# dds.net
KiCad netlist of a schematic drawn in Altium Designer
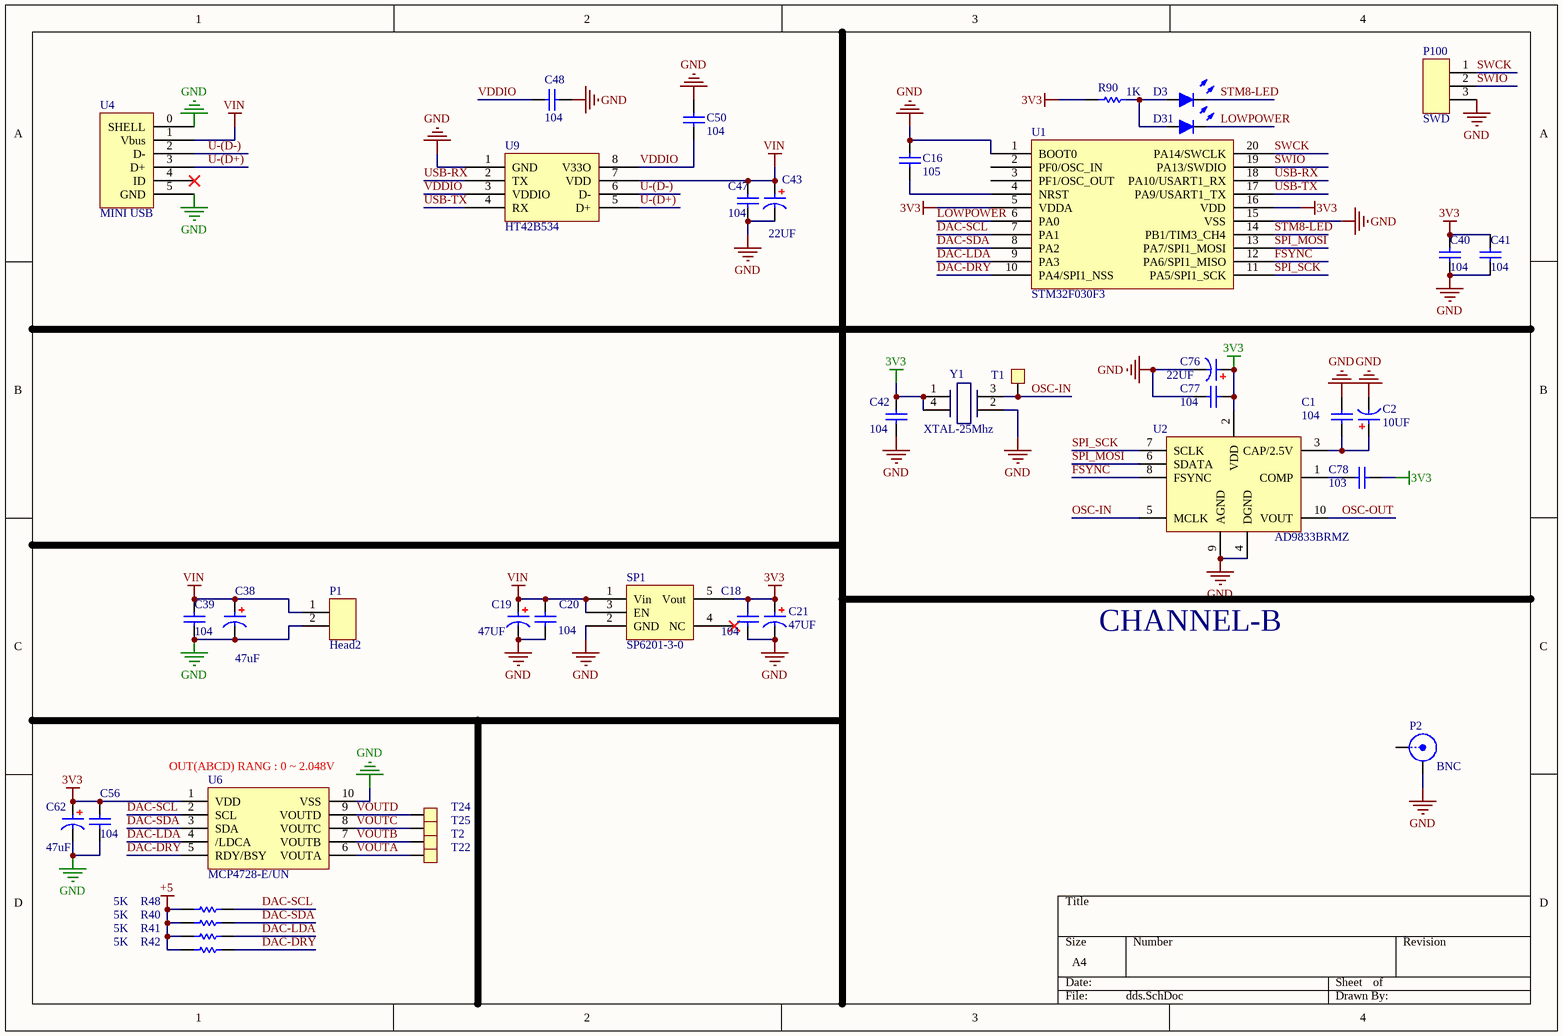
[diagram p0: dds.SchDoc]

(export (version "E")
  (design (tool "Eeschema 10.0.6"))
  (components
    (comp (ref "C1")
      (value "C104")
      (footprint "0402")
      (description "贴片电容")
      (fields (field (name "ALTIUM_UNNAMED_1") "104"))
      (libsource (lib "OKmeSchLibrary") (part "C0.1uF"))
    )
    (comp (ref "C2")
      (value "10UF")
      (footprint "0603C")
      (description "贴片电容")
      (fields (field (name "ALTIUM_UNNAMED_1") "10UF"))
      (libsource (lib "") (part "C10uF_1"))
    )
    (comp (ref "C16")
      (value "C1uF")
      (footprint "0603C")
      (fields (field (name "ALTIUM_UNNAMED_1") "105"))
      (libsource (lib "OKmeSchLibrary") (part "C0.1uF"))
    )
    (comp (ref "C18")
      (value "C104")
      (footprint "0402")
      (description "贴片电容")
      (fields (field (name "ALTIUM_UNNAMED_1") "104"))
      (libsource (lib "OKmeSchLibrary") (part "C0.1uF"))
    )
    (comp (ref "C19")
      (value "47UF")
      (footprint "CAP-T-3216")
      (description "贴片电容")
      (fields (field (name "ALTIUM_UNNAMED_1") "47UF"))
      (libsource (lib "") (part "C10uF_1"))
    )
    (comp (ref "C20")
      (value "C104")
      (footprint "0402")
      (description "贴片电容")
      (fields (field (name "ALTIUM_UNNAMED_1") "104"))
      (libsource (lib "OKmeSchLibrary") (part "C0.1uF"))
    )
    (comp (ref "C21")
      (value "47UF")
      (footprint "CAP-T-3216")
      (description "贴片电容")
      (fields (field (name "ALTIUM_UNNAMED_1") "47UF"))
      (libsource (lib "") (part "C10uF_1"))
    )
    (comp (ref "C38")
      (value "47uF")
      (footprint "CAP-T-3216")
      (description "贴片电容")
      (fields (field (name "ALTIUM_UNNAMED_1") "47uF"))
      (libsource (lib "") (part "C10uF_1"))
    )
    (comp (ref "C39")
      (value "C0.1uF")
      (footprint "0402")
      (fields (field (name "ALTIUM_UNNAMED_1") "104"))
      (libsource (lib "OKmeSchLibrary") (part "C0.1uF"))
    )
    (comp (ref "C40")
      (value "C0.1uF")
      (footprint "0402")
      (fields (field (name "ALTIUM_UNNAMED_1") "104"))
      (libsource (lib "OKmeSchLibrary") (part "C0.1uF"))
    )
    (comp (ref "C41")
      (value "C0.1uF")
      (footprint "0402")
      (fields (field (name "ALTIUM_UNNAMED_1") "104"))
      (libsource (lib "OKmeSchLibrary") (part "C0.1uF"))
    )
    (comp (ref "C42")
      (value "C0.1uF")
      (footprint "0402")
      (fields (field (name "ALTIUM_UNNAMED_1") "104"))
      (libsource (lib "OKmeSchLibrary") (part "C0.1uF"))
    )
    (comp (ref "C43")
      (value "22UF")
      (footprint "0603C")
      (fields (field (name "ALTIUM_UNNAMED_1") "22UF"))
      (libsource (lib "OKmeSchLibrary") (part "C100uF"))
    )
    (comp (ref "C47")
      (value "104")
      (footprint "0402")
      (fields (field (name "ALTIUM_UNNAMED_1") "104"))
      (libsource (lib "OKmeSchLibrary") (part "C0.1uF"))
    )
    (comp (ref "C48")
      (value "104")
      (footprint "0402")
      (fields (field (name "ALTIUM_UNNAMED_1") "104"))
      (libsource (lib "OKmeSchLibrary") (part "C0.1uF"))
    )
    (comp (ref "C50")
      (value "104")
      (footprint "0402")
      (fields (field (name "ALTIUM_UNNAMED_1") "104"))
      (libsource (lib "OKmeSchLibrary") (part "C0.1uF"))
    )
    (comp (ref "C56")
      (value "C0.1uF")
      (footprint "0402")
      (fields (field (name "ALTIUM_UNNAMED_1") "104"))
      (libsource (lib "OKmeSchLibrary") (part "C0.1uF"))
    )
    (comp (ref "C62")
      (value "47uF")
      (footprint "CAP-T-3216")
      (description "贴片电容")
      (fields (field (name "ALTIUM_UNNAMED_1") "47uF"))
      (libsource (lib "") (part "C10uF_1"))
    )
    (comp (ref "C76")
      (value "22UF")
      (footprint "0603C")
      (description "贴片电容")
      (fields (field (name "ALTIUM_UNNAMED_1") "22UF"))
      (libsource (lib "OKmeSchLibrary") (part "C10uF"))
    )
    (comp (ref "C77")
      (value "C104")
      (footprint "0402")
      (description "贴片电容")
      (fields (field (name "ALTIUM_UNNAMED_1") "104"))
      (libsource (lib "OKmeSchLibrary") (part "C0.1uF"))
    )
    (comp (ref "C78")
      (value "C103")
      (footprint "0402")
      (description "贴片电容")
      (fields (field (name "ALTIUM_UNNAMED_1") "103"))
      (libsource (lib "OKmeSchLibrary") (part "C0.1uF"))
    )
    (comp (ref "D3") (value "LED-G") (footprint "LED") (libsource (lib "OKmeSchLibrary") (part "LED")))
    (comp (ref "D31") (value "LED-R") (footprint "LED") (libsource (lib "OKmeSchLibrary") (part "LED")))
    (comp (ref "P1") (value "Head2") (footprint "HEAD2") (libsource (lib "OKmeSchLibrary") (part "Head2")))
    (comp (ref "P2")
      (value "BNC")
      (footprint "BNC-OSC")
      (description "BNC Elbow Connector")
      (fields (field (name "PUBLISHER") "Altium Limited"))
      (libsource (lib "Miscellaneous Connectors") (part "BNC"))
    )
    (comp (ref "P100")
      (value "SWD")
      (footprint "head*3 - duplicate")
      (libsource (lib "OKmeSchLibrary") (part "head*3"))
    )
    (comp (ref "R40")
      (value "R5K")
      (footprint "0402")
      (fields (field (name "ALTIUM_UNNAMED_1") "5K"))
      (libsource (lib "OKmeSchLibrary") (part "R10K"))
    )
    (comp (ref "R41")
      (value "R5K")
      (footprint "0402")
      (fields (field (name "ALTIUM_UNNAMED_1") "5K"))
      (libsource (lib "OKmeSchLibrary") (part "R10K"))
    )
    (comp (ref "R42")
      (value "R5K")
      (footprint "0402")
      (fields (field (name "ALTIUM_UNNAMED_1") "5K"))
      (libsource (lib "OKmeSchLibrary") (part "R10K"))
    )
    (comp (ref "R48")
      (value "R5K")
      (footprint "0402")
      (fields (field (name "ALTIUM_UNNAMED_1") "5K"))
      (libsource (lib "OKmeSchLibrary") (part "R10K"))
    )
    (comp (ref "R90")
      (value "R1K")
      (footprint "0603R")
      (fields (field (name "ALTIUM_UNNAMED_1") "1K"))
      (libsource (lib "OKmeSchLibrary") (part "R1K"))
    )
    (comp (ref "SP1")
      (value "SP6201-3-0")
      (footprint "SOT23-5")
      (libsource (lib "OKmeSchLibrary") (part "SP6201"))
    )
    (comp (ref "T1") (value "TP") (footprint "TEST_POINT") (libsource (lib "") (part "TP_1")))
    (comp (ref "T2") (value "TP") (footprint "TEST_POINT") (libsource (lib "OKmeSchLibrary") (part "TP")))
    (comp (ref "T22") (value "TP") (footprint "TEST_POINT") (libsource (lib "OKmeSchLibrary") (part "TP")))
    (comp (ref "T24") (value "TP") (footprint "TEST_POINT") (libsource (lib "OKmeSchLibrary") (part "TP")))
    (comp (ref "T25") (value "TP") (footprint "TEST_POINT") (libsource (lib "OKmeSchLibrary") (part "TP")))
    (comp (ref "U1")
      (value "STM32F030F3")
      (footprint "TSSOP20")
      (libsource (lib "OKmeSchLibrary") (part "STM32F030F4"))
    )
    (comp (ref "U2") (value "AD9833BRMZ") (footprint "MSOP10") (libsource (lib "osc_dev") (part "AD9833")))
    (comp (ref "U4")
      (value "MINI USB")
      (footprint "Micro_USB_t")
      (libsource (lib "OKmeSchLibrary") (part "MINI USB"))
    )
    (comp (ref "U6")
      (value "MCP4728-E/UN")
      (footprint "MSOP10")
      (libsource (lib "osc_dev") (part "MCP4728-E/UN"))
    )
    (comp (ref "U9")
      (value "HT42B534")
      (footprint "SOP-8")
      (libsource (lib "OKmeSchLibrary") (part "HT42B534"))
    )
    (comp (ref "Y1")
      (value "XTAL-25Mhz")
      (footprint "XTAL3225")
      (libsource (lib "osc_dev") (part "XTAL-100Mhz"))
    )
  )
  (nets
    (net (code "1") (name "+5") (class "Default")
      (node (ref "R40") (pin "1") (pinfunction "1_1") (pintype "passive"))
      (node (ref "R41") (pin "1") (pinfunction "1_1") (pintype "passive"))
      (node (ref "R42") (pin "1") (pinfunction "1_1") (pintype "passive"))
      (node (ref "R48") (pin "2") (pinfunction "2_2") (pintype "passive"))
    )
    (net (code "2") (name "/DAC-DRY") (class "Default")
      (node (ref "R42") (pin "2") (pinfunction "2_2") (pintype "passive"))
      (node (ref "U1") (pin "10") (pinfunction "PA4/SPI1_NSS_10") (pintype "passive"))
      (node (ref "U6") (pin "5") (pinfunction "RDY/BSY_5") (pintype "passive"))
    )
    (net (code "3") (name "/DAC-LDA") (class "Default")
      (node (ref "R41") (pin "2") (pinfunction "2_2") (pintype "passive"))
      (node (ref "U1") (pin "9") (pinfunction "PA3_9") (pintype "passive"))
      (node (ref "U6") (pin "4") (pinfunction "/LDCA_4") (pintype "passive"))
    )
    (net (code "4") (name "/DAC-SCL") (class "Default")
      (node (ref "R48") (pin "1") (pinfunction "1_1") (pintype "passive"))
      (node (ref "U1") (pin "7") (pinfunction "PA1_7") (pintype "passive"))
      (node (ref "U6") (pin "2") (pinfunction "SCL_2") (pintype "passive"))
    )
    (net (code "5") (name "/DAC-SDA") (class "Default")
      (node (ref "R40") (pin "2") (pinfunction "2_2") (pintype "passive"))
      (node (ref "U1") (pin "8") (pinfunction "PA2_8") (pintype "passive"))
      (node (ref "U6") (pin "3") (pinfunction "SDA_3") (pintype "passive"))
    )
    (net (code "6") (name "/FSYNC") (class "Default")
      (node (ref "U1") (pin "12") (pinfunction "PA6/SPI1_MISO_12") (pintype "passive"))
      (node (ref "U2") (pin "8") (pinfunction "FSYNC_8") (pintype "passive"))
    )
    (net (code "7") (name "/LOWPOWER") (class "Default")
      (node (ref "D31") (pin "2") (pinfunction "K_2") (pintype "passive"))
      (node (ref "U1") (pin "6") (pinfunction "PA0_6") (pintype "passive"))
    )
    (net (code "8") (name "/OSC-IN") (class "Default")
      (node (ref "T1") (pin "1") (pinfunction "R_1") (pintype "passive"))
      (node (ref "U2") (pin "5") (pinfunction "MCLK_5") (pintype "passive"))
      (node (ref "Y1") (pin "3") (pinfunction "3_3") (pintype "passive"))
    )
    (net (code "9") (name "/OSC-OUT") (class "Default")
      (node (ref "U2") (pin "10") (pinfunction "VOUT_10") (pintype "passive"))
    )
    (net (code "10") (name "/SPI_MOSI") (class "Default")
      (node (ref "U1") (pin "13") (pinfunction "PA7/SPI1_MOSI_13") (pintype "passive"))
      (node (ref "U2") (pin "6") (pinfunction "SDATA_6") (pintype "passive"))
    )
    (net (code "11") (name "/SPI_SCK") (class "Default")
      (node (ref "U1") (pin "11") (pinfunction "PA5/SPI1_SCK_11") (pintype "passive"))
      (node (ref "U2") (pin "7") (pinfunction "SCLK_7") (pintype "passive"))
    )
    (net (code "12") (name "/STM8-LED") (class "Default")
      (node (ref "D3") (pin "2") (pinfunction "K_2") (pintype "passive"))
      (node (ref "U1") (pin "14") (pinfunction "PB1/TIM3_CH4_14") (pintype "passive"))
    )
    (net (code "13") (name "/SWCK") (class "Default")
      (node (ref "P100") (pin "1") (pinfunction "1_1") (pintype "passive"))
      (node (ref "U1") (pin "20") (pinfunction "PA14/SWCLK_20") (pintype "passive"))
    )
    (net (code "14") (name "/SWIO") (class "Default")
      (node (ref "P100") (pin "2") (pinfunction "2_2") (pintype "passive"))
      (node (ref "U1") (pin "19") (pinfunction "PA13/SWDIO_19") (pintype "passive"))
    )
    (net (code "15") (name "/U-(D+)") (class "Default")
      (node (ref "U4") (pin "3") (pinfunction "D+_3") (pintype "passive"))
      (node (ref "U9") (pin "5") (pinfunction "D+_5") (pintype "passive"))
    )
    (net (code "16") (name "/U-(D-)") (class "Default")
      (node (ref "U4") (pin "2") (pinfunction "D-_2") (pintype "passive"))
      (node (ref "U9") (pin "6") (pinfunction "D-_6") (pintype "passive"))
    )
    (net (code "17") (name "/USB-RX") (class "Default")
      (node (ref "U1") (pin "18") (pinfunction "PA10/USART1_RX_18") (pintype "passive"))
      (node (ref "U9") (pin "2") (pinfunction "TX_2") (pintype "passive"))
    )
    (net (code "18") (name "/USB-TX") (class "Default")
      (node (ref "U1") (pin "17") (pinfunction "PA9/USART1_TX_17") (pintype "passive"))
      (node (ref "U9") (pin "4") (pinfunction "RX_4") (pintype "passive"))
    )
    (net (code "19") (name "/VDDIO") (class "Default")
      (node (ref "C48") (pin "1") (pinfunction "1_1") (pintype "passive"))
      (node (ref "C50") (pin "1") (pinfunction "1_1") (pintype "passive"))
      (node (ref "U9") (pin "3") (pinfunction "VDDIO_3") (pintype "passive"))
      (node (ref "U9") (pin "8") (pinfunction "V33O_8") (pintype "passive"))
    )
    (net (code "20") (name "/VOUTA") (class "Default")
      (node (ref "T22") (pin "1") (pinfunction "R_1") (pintype "passive"))
      (node (ref "U6") (pin "6") (pinfunction "VOUTA_6") (pintype "passive"))
    )
    (net (code "21") (name "/VOUTB") (class "Default")
      (node (ref "T2") (pin "1") (pinfunction "R_1") (pintype "passive"))
      (node (ref "U6") (pin "7") (pinfunction "VOUTB_7") (pintype "passive"))
    )
    (net (code "22") (name "/VOUTC") (class "Default")
      (node (ref "T25") (pin "1") (pinfunction "R_1") (pintype "passive"))
      (node (ref "U6") (pin "8") (pinfunction "VOUTC_8") (pintype "passive"))
    )
    (net (code "23") (name "/VOUTD") (class "Default")
      (node (ref "T24") (pin "1") (pinfunction "R_1") (pintype "passive"))
      (node (ref "U6") (pin "9") (pinfunction "VOUTD_9") (pintype "passive"))
    )
    (net (code "24") (name "3V3") (class "Default")
      (node (ref "C18") (pin "1") (pinfunction "1_1") (pintype "passive"))
      (node (ref "C21") (pin "1") (pinfunction "1_1") (pintype "passive"))
      (node (ref "C40") (pin "1") (pinfunction "1_1") (pintype "passive"))
      (node (ref "C41") (pin "1") (pinfunction "1_1") (pintype "passive"))
      (node (ref "C42") (pin "2") (pinfunction "2_2") (pintype "passive"))
      (node (ref "C56") (pin "1") (pinfunction "1_1") (pintype "passive"))
      (node (ref "C62") (pin "1") (pinfunction "1_1") (pintype "passive"))
      (node (ref "C76") (pin "1") (pinfunction "1_1") (pintype "passive"))
      (node (ref "C77") (pin "1") (pinfunction "1_1") (pintype "passive"))
      (node (ref "C78") (pin "1") (pinfunction "1_1") (pintype "passive"))
      (node (ref "R90") (pin "1") (pinfunction "1_1") (pintype "passive"))
      (node (ref "SP1") (pin "5") (pinfunction "Vout_5") (pintype "power_in"))
      (node (ref "U1") (pin "16") (pinfunction "VDD_16") (pintype "passive"))
      (node (ref "U1") (pin "5") (pinfunction "VDDA_5") (pintype "passive"))
      (node (ref "U2") (pin "2") (pinfunction "VDD_2") (pintype "passive"))
      (node (ref "U6") (pin "1") (pinfunction "VDD_1") (pintype "passive"))
      (node (ref "Y1") (pin "1") (pinfunction "1_1") (pintype "passive"))
      (node (ref "Y1") (pin "4") (pinfunction "4_4") (pintype "passive"))
    )
    (net (code "25") (name "GND") (class "Default")
      (node (ref "C1") (pin "2") (pinfunction "2_2") (pintype "passive"))
      (node (ref "C16") (pin "1") (pinfunction "1_1") (pintype "passive"))
      (node (ref "C18") (pin "2") (pinfunction "2_2") (pintype "passive"))
      (node (ref "C19") (pin "2") (pinfunction "2_2") (pintype "passive"))
      (node (ref "C2") (pin "2") (pinfunction "2_2") (pintype "passive"))
      (node (ref "C20") (pin "2") (pinfunction "2_2") (pintype "passive"))
      (node (ref "C21") (pin "2") (pinfunction "2_2") (pintype "passive"))
      (node (ref "C38") (pin "2") (pinfunction "2_2") (pintype "passive"))
      (node (ref "C39") (pin "2") (pinfunction "2_2") (pintype "passive"))
      (node (ref "C40") (pin "2") (pinfunction "2_2") (pintype "passive"))
      (node (ref "C41") (pin "2") (pinfunction "2_2") (pintype "passive"))
      (node (ref "C42") (pin "1") (pinfunction "1_1") (pintype "passive"))
      (node (ref "C43") (pin "2") (pinfunction "2_2") (pintype "passive"))
      (node (ref "C47") (pin "2") (pinfunction "2_2") (pintype "passive"))
      (node (ref "C48") (pin "2") (pinfunction "2_2") (pintype "passive"))
      (node (ref "C50") (pin "2") (pinfunction "2_2") (pintype "passive"))
      (node (ref "C56") (pin "2") (pinfunction "2_2") (pintype "passive"))
      (node (ref "C62") (pin "2") (pinfunction "2_2") (pintype "passive"))
      (node (ref "C76") (pin "2") (pinfunction "2_2") (pintype "passive"))
      (node (ref "C77") (pin "2") (pinfunction "2_2") (pintype "passive"))
      (node (ref "P1") (pin "2") (pinfunction "2_2") (pintype "passive"))
      (node (ref "P100") (pin "3") (pinfunction "3_3") (pintype "passive"))
      (node (ref "P2") (pin "2") (pinfunction "Y_2") (pintype "passive"))
      (node (ref "SP1") (pin "2") (pinfunction "GND_2") (pintype "power_in"))
      (node (ref "U1") (pin "1") (pinfunction "BOOT0_1") (pintype "passive"))
      (node (ref "U1") (pin "15") (pinfunction "VSS_15") (pintype "passive"))
      (node (ref "U2") (pin "4") (pinfunction "DGND_4") (pintype "passive"))
      (node (ref "U2") (pin "9") (pinfunction "AGND_9") (pintype "passive"))
      (node (ref "U4") (pin "0") (pinfunction "SHELL_0") (pintype "passive"))
      (node (ref "U4") (pin "5") (pinfunction "GND_5") (pintype "power_in"))
      (node (ref "U6") (pin "10") (pinfunction "VSS_10") (pintype "passive"))
      (node (ref "U9") (pin "1") (pinfunction "GND_1") (pintype "passive"))
      (node (ref "Y1") (pin "2") (pinfunction "2_2") (pintype "passive"))
    )
    (net (code "26") (name "Net-(D3-A)") (class "Default")
      (node (ref "D3") (pin "1") (pinfunction "A_1") (pintype "passive"))
      (node (ref "D31") (pin "1") (pinfunction "A_1") (pintype "passive"))
      (node (ref "R90") (pin "2") (pinfunction "2_2") (pintype "passive"))
    )
    (net (code "27") (name "Net-(U1-NRST)") (class "Default")
      (node (ref "C16") (pin "2") (pinfunction "2_2") (pintype "passive"))
      (node (ref "U1") (pin "4") (pinfunction "NRST_4") (pintype "passive"))
    )
    (net (code "28") (name "Net-(U2-CAP{slash}2.5V)") (class "Default")
      (node (ref "C1") (pin "1") (pinfunction "1_1") (pintype "passive"))
      (node (ref "C2") (pin "1") (pinfunction "1_1") (pintype "passive"))
      (node (ref "U2") (pin "3") (pinfunction "CAP/2.5V_3") (pintype "passive"))
    )
    (net (code "29") (name "Net-(U2-COMP)") (class "Default")
      (node (ref "C78") (pin "2") (pinfunction "2_2") (pintype "passive"))
      (node (ref "U2") (pin "1") (pinfunction "COMP_1") (pintype "passive"))
    )
    (net (code "30") (name "VIN") (class "Default")
      (node (ref "C19") (pin "1") (pinfunction "1_1") (pintype "passive"))
      (node (ref "C20") (pin "1") (pinfunction "1_1") (pintype "passive"))
      (node (ref "C38") (pin "1") (pinfunction "1_1") (pintype "passive"))
      (node (ref "C39") (pin "1") (pinfunction "1_1") (pintype "passive"))
      (node (ref "C43") (pin "1") (pinfunction "1_1") (pintype "passive"))
      (node (ref "C47") (pin "1") (pinfunction "1_1") (pintype "passive"))
      (node (ref "P1") (pin "1") (pinfunction "1_1") (pintype "passive"))
      (node (ref "SP1") (pin "1") (pinfunction "Vin_1") (pintype "power_in"))
      (node (ref "SP1") (pin "3") (pinfunction "EN_3") (pintype "passive"))
      (node (ref "U4") (pin "1") (pinfunction "Vbus_1") (pintype "power_in"))
      (node (ref "U9") (pin "7") (pinfunction "VDD_7") (pintype "passive"))
    )
    (net (code "31") (name "unconnected-(P2-X-Pad1)") (class "Default")
      (node (ref "P2") (pin "1") (pinfunction "X_1") (pintype "passive"))
    )
    (net (code "32") (name "unconnected-(SP1-NC-Pad4)") (class "Default")
      (node (ref "SP1") (pin "4") (pinfunction "NC_4") (pintype "passive+no_connect"))
    )
    (net (code "33") (name "unconnected-(U1-PF0{slash}OSC_IN-Pad2)") (class "Default")
      (node (ref "U1") (pin "2") (pinfunction "PF0/OSC_IN_2") (pintype "passive"))
    )
    (net (code "34") (name "unconnected-(U1-PF1{slash}OSC_OUT-Pad3)") (class "Default")
      (node (ref "U1") (pin "3") (pinfunction "PF1/OSC_OUT_3") (pintype "passive"))
    )
    (net (code "35") (name "unconnected-(U4-ID-Pad4)") (class "Default")
      (node (ref "U4") (pin "4") (pinfunction "ID_4") (pintype "passive+no_connect"))
    )
  )
)
